# Sensor_compartment_Schematic.net
KiCad netlist of a schematic drawn in Altium Designer
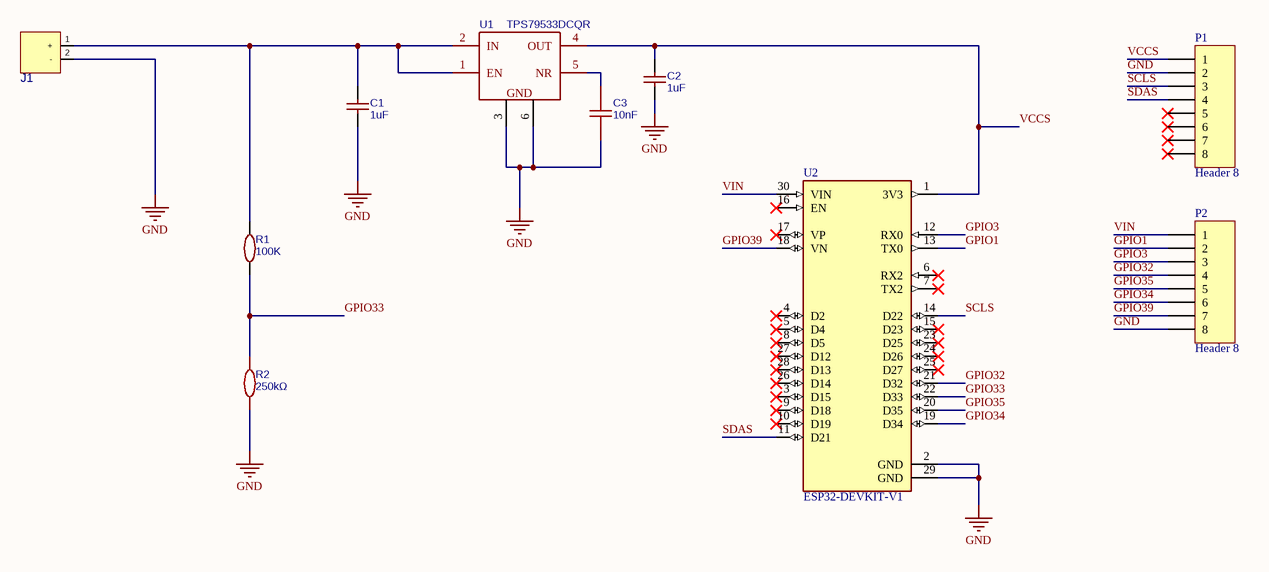
[diagram p0: Sensor_compartment_Schematic.SchDoc]

(export (version "E")
  (design (tool "Eeschema 10.0.6"))
  (components
    (comp (ref "C1")
      (value "1uF")
      (footprint "1uF ceramic cap")
      (fields
        (field (name "BOM_MANUFACTURER PART") "0805F105Z160CT")
        (field (name "BOM_SUPPLIER PART") "C123629")
        (field (name "CONTRIBUTOR") "LCSC")
      )
      (libsource (lib "ComponantLib") (part "1uF"))
    )
    (comp (ref "C2")
      (value "1uF")
      (footprint "1uF ceramic cap")
      (fields
        (field (name "BOM_MANUFACTURER PART") "0805F105Z160CT")
        (field (name "BOM_SUPPLIER PART") "C123629")
        (field (name "CONTRIBUTOR") "LCSC")
      )
      (libsource (lib "ComponantLib") (part "1uF"))
    )
    (comp (ref "C3")
      (value "10nF")
      (footprint "1nF cap")
      (fields
        (field (name "BOM_SUPPLIER PART") "C388908")
        (field (name "BOM_MANUFACTURER PART") "GCM216R71H103KA37D")
        (field (name "CONTRIBUTOR") "LCSC")
      )
      (libsource (lib "ComponantLib") (part "10nF"))
    )
    (comp (ref "J1")
      (value "*")
      (footprint "BATTERY_PAD")
      (description "Battery Connector")
      (fields (field (name "MANUFACTURER") "???"))
      (libsource (lib "ComponantLib") (part "BATTERY_PAD"))
    )
    (comp (ref "P1")
      (value "Header 8")
      (footprint "HDR1X8")
      (description "Header, 8-Pin")
      (fields (field (name "PUBLISHER") "Altium Limited"))
      (libsource (lib "ComponantLib") (part "Header 8"))
    )
    (comp (ref "P2")
      (value "Header 8")
      (footprint "HDR1X8")
      (description "Header, 8-Pin")
      (fields (field (name "PUBLISHER") "Altium Limited"))
      (libsource (lib "Miscellaneous Connectors") (part "Header 8"))
    )
    (comp (ref "R1")
      (value "100K")
      (footprint "R100K")
      (fields
        (field (name "BOM_MANUFACTURER PART") "RC0805FR-07100KL")
        (field (name "BOM_SUPPLIER PART") "C96346")
      )
      (libsource (lib "ComponantLib") (part "100K"))
    )
    (comp (ref "R2")
      (value "250kΩ")
      (footprint "R250K")
      (fields
        (field (name "BOM_SUPPLIER PART") "C374782")
        (field (name "BOM_MANUFACTURER PART") "AR06BTC2503")
        (field (name "CONTRIBUTOR") "LCSC")
      )
      (libsource (lib "ComponantLib") (part "250kΩ"))
    )
    (comp (ref "U1")
      (value "TPS79533DCQR")
      (footprint "TPS79533DCQR")
      (fields (field (name "BOM_SUPPLIER PART") "C28669"))
      (libsource (lib "ComponantLib") (part "TPS79533DCQR"))
    )
    (comp (ref "U2")
      (value "ESP32-DEVKIT-V1")
      (footprint "MODULE_ESP32_DEVKIT_V1")
      (libsource (lib "ComponantLib") (part "ESP32-DEVKIT-V1"))
    )
  )
  (nets
    (net (code "1") (name "/GPIO1") (class "Default")
      (node (ref "P2") (pin "2") (pinfunction "2_2") (pintype "passive"))
      (node (ref "U2") (pin "13") (pinfunction "TX0_13") (pintype "output"))
    )
    (net (code "2") (name "/GPIO3") (class "Default")
      (node (ref "P2") (pin "3") (pinfunction "3_3") (pintype "passive"))
      (node (ref "U2") (pin "12") (pinfunction "RX0_12") (pintype "input"))
    )
    (net (code "3") (name "/GPIO32") (class "Default")
      (node (ref "P2") (pin "4") (pinfunction "4_4") (pintype "passive"))
      (node (ref "U2") (pin "21") (pinfunction "D32_21") (pintype "bidirectional"))
    )
    (net (code "4") (name "/GPIO33") (class "Default")
      (node (ref "R1") (pin "1") (pinfunction "1_1") (pintype "passive"))
      (node (ref "R2") (pin "2") (pinfunction "2_2") (pintype "passive"))
      (node (ref "U2") (pin "22") (pinfunction "D33_22") (pintype "bidirectional"))
    )
    (net (code "5") (name "/GPIO34") (class "Default")
      (node (ref "P2") (pin "6") (pinfunction "6_6") (pintype "passive"))
      (node (ref "U2") (pin "19") (pinfunction "D34_19") (pintype "bidirectional"))
    )
    (net (code "6") (name "/GPIO35") (class "Default")
      (node (ref "P2") (pin "5") (pinfunction "5_5") (pintype "passive"))
      (node (ref "U2") (pin "20") (pinfunction "D35_20") (pintype "bidirectional"))
    )
    (net (code "7") (name "/GPIO39") (class "Default")
      (node (ref "P2") (pin "7") (pinfunction "7_7") (pintype "passive"))
      (node (ref "U2") (pin "18") (pinfunction "VN_18") (pintype "bidirectional"))
    )
    (net (code "8") (name "/SCLS") (class "Default")
      (node (ref "P1") (pin "3") (pinfunction "3_3") (pintype "passive"))
      (node (ref "U2") (pin "14") (pinfunction "D22_14") (pintype "bidirectional"))
    )
    (net (code "9") (name "/SDAS") (class "Default")
      (node (ref "P1") (pin "4") (pinfunction "4_4") (pintype "passive"))
      (node (ref "U2") (pin "11") (pinfunction "D21_11") (pintype "bidirectional"))
    )
    (net (code "10") (name "/VCCS") (class "Default")
      (node (ref "C2") (pin "2") (pinfunction "2_2") (pintype "passive"))
      (node (ref "P1") (pin "1") (pinfunction "1_1") (pintype "passive"))
      (node (ref "U1") (pin "4") (pinfunction "OUT_4") (pintype "passive"))
      (node (ref "U2") (pin "1") (pinfunction "3V3_1") (pintype "output"))
    )
    (net (code "11") (name "/VIN") (class "Default")
      (node (ref "P2") (pin "1") (pinfunction "1_1") (pintype "passive"))
      (node (ref "U2") (pin "30") (pinfunction "VIN_30") (pintype "input"))
    )
    (net (code "12") (name "GND") (class "Default")
      (node (ref "C1") (pin "1") (pinfunction "1_1") (pintype "passive"))
      (node (ref "C2") (pin "1") (pinfunction "1_1") (pintype "passive"))
      (node (ref "C3") (pin "1") (pinfunction "1_1") (pintype "passive"))
      (node (ref "J1") (pin "2") (pinfunction "-_2") (pintype "passive"))
      (node (ref "P1") (pin "2") (pinfunction "2_2") (pintype "passive"))
      (node (ref "P2") (pin "8") (pinfunction "8_8") (pintype "passive"))
      (node (ref "R2") (pin "1") (pinfunction "1_1") (pintype "passive"))
      (node (ref "U1") (pin "3") (pinfunction "GND_3") (pintype "passive"))
      (node (ref "U1") (pin "6") (pinfunction "GND_6") (pintype "passive"))
      (node (ref "U2") (pin "2") (pinfunction "GND_2") (pintype "power_in"))
      (node (ref "U2") (pin "29") (pinfunction "GND_29") (pintype "power_in"))
    )
    (net (code "13") (name "Net-(J1-+)") (class "Default")
      (node (ref "C1") (pin "2") (pinfunction "2_2") (pintype "passive"))
      (node (ref "J1") (pin "1") (pinfunction "+_1") (pintype "passive"))
      (node (ref "R1") (pin "2") (pinfunction "2_2") (pintype "passive"))
      (node (ref "U1") (pin "1") (pinfunction "EN_1") (pintype "passive"))
      (node (ref "U1") (pin "2") (pinfunction "IN_2") (pintype "passive"))
    )
    (net (code "14") (name "Net-(U1-NR)") (class "Default")
      (node (ref "C3") (pin "2") (pinfunction "2_2") (pintype "passive"))
      (node (ref "U1") (pin "5") (pinfunction "NR_5") (pintype "passive"))
    )
    (net (code "15") (name "unconnected-(P1-Pad5)") (class "Default")
      (node (ref "P1") (pin "5") (pinfunction "5_5") (pintype "passive+no_connect"))
    )
    (net (code "16") (name "unconnected-(P1-Pad6)") (class "Default")
      (node (ref "P1") (pin "6") (pinfunction "6_6") (pintype "passive+no_connect"))
    )
    (net (code "17") (name "unconnected-(P1-Pad7)") (class "Default")
      (node (ref "P1") (pin "7") (pinfunction "7_7") (pintype "passive+no_connect"))
    )
    (net (code "18") (name "unconnected-(P1-Pad8)") (class "Default")
      (node (ref "P1") (pin "8") (pinfunction "8_8") (pintype "passive+no_connect"))
    )
    (net (code "19") (name "unconnected-(U2-D2-Pad4)") (class "Default")
      (node (ref "U2") (pin "4") (pinfunction "D2_4") (pintype "bidirectional+no_connect"))
    )
    (net (code "20") (name "unconnected-(U2-D4-Pad5)") (class "Default")
      (node (ref "U2") (pin "5") (pinfunction "D4_5") (pintype "bidirectional+no_connect"))
    )
    (net (code "21") (name "unconnected-(U2-D5-Pad8)") (class "Default")
      (node (ref "U2") (pin "8") (pinfunction "D5_8") (pintype "bidirectional+no_connect"))
    )
    (net (code "22") (name "unconnected-(U2-D12-Pad27)") (class "Default")
      (node (ref "U2") (pin "27") (pinfunction "D12_27") (pintype "bidirectional+no_connect"))
    )
    (net (code "23") (name "unconnected-(U2-D13-Pad28)") (class "Default")
      (node (ref "U2") (pin "28") (pinfunction "D13_28") (pintype "bidirectional+no_connect"))
    )
    (net (code "24") (name "unconnected-(U2-D14-Pad26)") (class "Default")
      (node (ref "U2") (pin "26") (pinfunction "D14_26") (pintype "bidirectional+no_connect"))
    )
    (net (code "25") (name "unconnected-(U2-D15-Pad3)") (class "Default")
      (node (ref "U2") (pin "3") (pinfunction "D15_3") (pintype "bidirectional+no_connect"))
    )
    (net (code "26") (name "unconnected-(U2-D18-Pad9)") (class "Default")
      (node (ref "U2") (pin "9") (pinfunction "D18_9") (pintype "bidirectional+no_connect"))
    )
    (net (code "27") (name "unconnected-(U2-D19-Pad10)") (class "Default")
      (node (ref "U2") (pin "10") (pinfunction "D19_10") (pintype "bidirectional+no_connect"))
    )
    (net (code "28") (name "unconnected-(U2-D23-Pad15)") (class "Default")
      (node (ref "U2") (pin "15") (pinfunction "D23_15") (pintype "bidirectional+no_connect"))
    )
    (net (code "29") (name "unconnected-(U2-D25-Pad23)") (class "Default")
      (node (ref "U2") (pin "23") (pinfunction "D25_23") (pintype "bidirectional+no_connect"))
    )
    (net (code "30") (name "unconnected-(U2-D26-Pad24)") (class "Default")
      (node (ref "U2") (pin "24") (pinfunction "D26_24") (pintype "bidirectional+no_connect"))
    )
    (net (code "31") (name "unconnected-(U2-D27-Pad25)") (class "Default")
      (node (ref "U2") (pin "25") (pinfunction "D27_25") (pintype "bidirectional+no_connect"))
    )
    (net (code "32") (name "unconnected-(U2-EN-Pad16)") (class "Default")
      (node (ref "U2") (pin "16") (pinfunction "EN_16") (pintype "input+no_connect"))
    )
    (net (code "33") (name "unconnected-(U2-RX2-Pad6)") (class "Default")
      (node (ref "U2") (pin "6") (pinfunction "RX2_6") (pintype "input+no_connect"))
    )
    (net (code "34") (name "unconnected-(U2-TX2-Pad7)") (class "Default")
      (node (ref "U2") (pin "7") (pinfunction "TX2_7") (pintype "output+no_connect"))
    )
    (net (code "35") (name "unconnected-(U2-VP-Pad17)") (class "Default")
      (node (ref "U2") (pin "17") (pinfunction "VP_17") (pintype "bidirectional+no_connect"))
    )
  )
)
